# SH2_-_MCU.net
KiCad netlist of a schematic drawn in Altium Designer
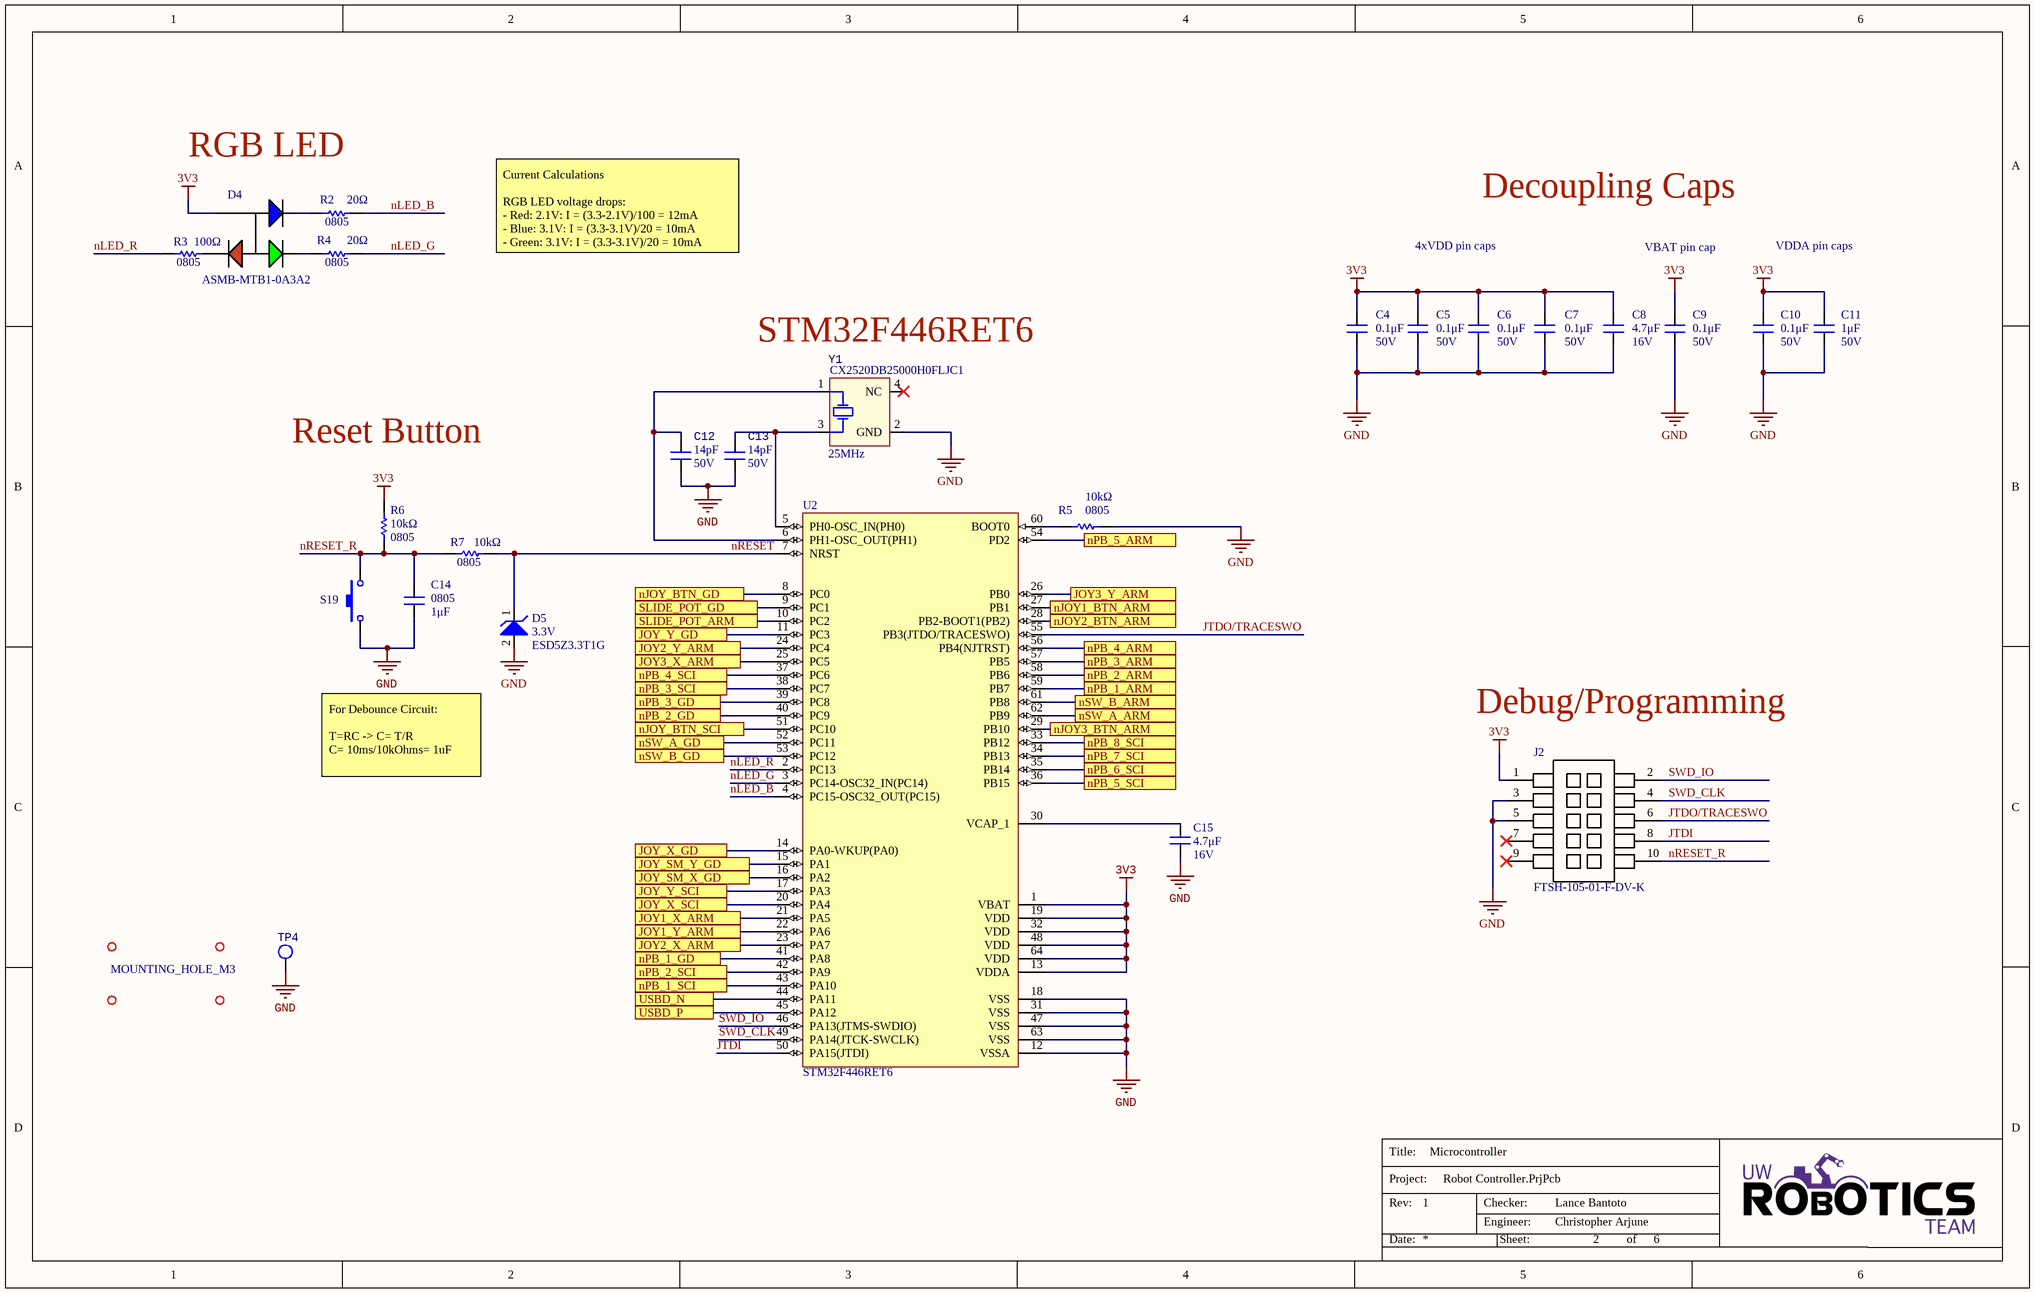
[diagram p0: SH2 - MCU.SchDoc]

(export (version "E")
  (design (tool "Eeschema 10.0.6"))
  (components
    (comp (ref "C4")
      (value "0.1μF")
      (footprint "CAP2012")
      (description "CAP CER 0.1UF 50V X7R 0805")
      (fields
        (field (name "VOLTAGE RATING") "50V")
        (field (name "LCSC PART #") "C49678")
        (field (name "Comment") "CAP_0.1uF_50V_0805")
      )
      (libsource (lib "UWRT_Schematic_Library_2020") (part "CAP_0.1uF_50V_0805"))
    )
    (comp (ref "C5")
      (value "0.1μF")
      (footprint "CAP2012")
      (description "CAP CER 0.1UF 50V X7R 0805")
      (fields
        (field (name "VOLTAGE RATING") "50V")
        (field (name "LCSC PART #") "C49678")
        (field (name "Comment") "CAP_0.1uF_50V_0805")
      )
      (libsource (lib "UWRT_Schematic_Library_2020") (part "CAP_0.1uF_50V_0805"))
    )
    (comp (ref "C6")
      (value "0.1μF")
      (footprint "CAP2012")
      (description "CAP CER 0.1UF 50V X7R 0805")
      (fields
        (field (name "VOLTAGE RATING") "50V")
        (field (name "LCSC PART #") "C49678")
        (field (name "Comment") "CAP_0.1uF_50V_0805")
      )
      (libsource (lib "UWRT_Schematic_Library_2020") (part "CAP_0.1uF_50V_0805"))
    )
    (comp (ref "C7")
      (value "0.1μF")
      (footprint "CAP2012")
      (description "CAP CER 0.1UF 50V X7R 0805")
      (fields
        (field (name "VOLTAGE RATING") "50V")
        (field (name "LCSC PART #") "C49678")
        (field (name "Comment") "CAP_0.1uF_50V_0805")
      )
      (libsource (lib "UWRT_Schematic_Library_2020") (part "CAP_0.1uF_50V_0805"))
    )
    (comp (ref "C8")
      (value "4.7μF")
      (footprint "CAP2012")
      (description "CAP CER 4.7UF 16V X5R 0805")
      (fields
        (field (name "VOLTAGE RATING") "16V")
        (field (name "LCSC PART #") "C1779")
        (field (name "Comment") "CAP_4.7uF_16V_0805")
      )
      (libsource (lib "UWRT_Schematic_Library_2020") (part "CAP_4.7uF_16V_0805"))
    )
    (comp (ref "C9")
      (value "0.1μF")
      (footprint "CAP2012")
      (description "CAP CER 0.1UF 50V X7R 0805")
      (fields
        (field (name "VOLTAGE RATING") "50V")
        (field (name "LCSC PART #") "C49678")
        (field (name "Comment") "CAP_0.1uF_50V_0805")
      )
      (libsource (lib "UWRT_Schematic_Library_2020") (part "CAP_0.1uF_50V_0805"))
    )
    (comp (ref "C10")
      (value "0.1μF")
      (footprint "CAP2012")
      (description "CAP CER 0.1UF 50V X7R 0805")
      (fields
        (field (name "VOLTAGE RATING") "50V")
        (field (name "LCSC PART #") "C49678")
        (field (name "Comment") "CAP_0.1uF_50V_0805")
      )
      (libsource (lib "UWRT_Schematic_Library_2020") (part "CAP_0.1uF_50V_0805"))
    )
    (comp (ref "C11")
      (value "1μF")
      (footprint "CAP2012")
      (description "CAP CER 1UF 50V X7R 0805")
      (fields
        (field (name "VOLTAGE RATING") "50V")
        (field (name "LCSC PART #") "C28323")
        (field (name "Comment") "CAP_1uF_50V_0805")
      )
      (libsource (lib "UWRT_Schematic_Library_2020") (part "CAP_1uF_50V_0805"))
    )
    (comp (ref "C12")
      (value "14pF")
      (footprint "CAP0603")
      (description "CAP CER 14PF 50V C0G/NP0 0603")
      (fields (field (name "VOLTAGE RATING") "50V") (field (name "Comment") "CAP_14pF_50V_0603"))
      (libsource (lib "UWRT_Schematic_Library_2020") (part "CAP_14pF_50V_0603"))
    )
    (comp (ref "C13")
      (value "14pF")
      (footprint "CAP0603")
      (description "CAP CER 14PF 50V C0G/NP0 0603")
      (fields (field (name "VOLTAGE RATING") "50V") (field (name "Comment") "CAP_14pF_50V_0603"))
      (libsource (lib "UWRT_Schematic_Library_2020") (part "CAP_14pF_50V_0603"))
    )
    (comp (ref "C14")
      (value "1μF")
      (footprint "CAP2012")
      (description "CAP CER 1UF 50V X7R 0805")
      (fields
        (field (name "LCSC PART #") "C28323")
        (field (name "PACKAGE/FOOTPRINT") "0805")
        (field (name "Comment") "CAP_1uF_50V_0805")
      )
      (libsource (lib "UWRT_Schematic_Library_2020") (part "CAP_1uF_50V_0805"))
    )
    (comp (ref "C15")
      (value "4.7μF")
      (footprint "CAP2012")
      (description "CAP CER 4.7UF 16V X5R 0805")
      (fields
        (field (name "VOLTAGE RATING") "16V")
        (field (name "LCSC PART #") "C1779")
        (field (name "Comment") "CAP_4.7uF_16V_0805")
      )
      (libsource (lib "UWRT_Schematic_Library_2020") (part "CAP_4.7uF_16V_0805"))
    )
    (comp (ref "D4")
      (value "LED_RGB")
      (footprint "LED_RGB")
      (description "LED RGB DIFFUSED 4PLCC SMD")
      (fields (field (name "MANUFACTURER PART NUMBER 1") "ASMB-MTB1-0A3A2"))
      (libsource (lib "UWRT_Schematic_Library_2020") (part "LED_RGB"))
    )
    (comp (ref "D5")
      (value "TVS_DIODE_UNIDIR_3.3V")
      (description "TVS DIODE 3.3V 14.1V SOD523")
      (fields
        (field (name "MANUFACTURER PART NUMBER 1") "ESD5Z3.3T1G")
        (field (name "LCSC PART #") "C61148")
        (field (name "VOLTAGE - REVERSE STANDOFF (TYP)") "3.3V")
      )
      (libsource (lib "UWRT_Schematic_Library_2020") (part "TVS_DIODE_UNIDIR_3.3V"))
    )
    (comp (ref "J2")
      (value "CON_PROGRAMMING")
      (footprint "FTSH-105-01-F-DV-K-P-TR")
      (description "CONN HEADER SMD 10POS 1.27MM")
      (fields (field (name "MANUFACTURER PART NUMBER 1") "FTSH-105-01-F-DV-K"))
      (libsource (lib "UWRT_Schematic_Library_2020") (part "CON_PROGRAMMING"))
    )
    (comp (ref "MH1")
      (value "MOUNTING_HOLE_M3")
      (footprint "MOUNTING_HOLE_3mm")
      (libsource (lib "UWRT_Schematic_Library_2020") (part "MOUNTING_HOLE_M3"))
    )
    (comp (ref "MH2")
      (value "MOUNTING_HOLE_M3")
      (footprint "MOUNTING_HOLE_3mm")
      (libsource (lib "UWRT_Schematic_Library_2020") (part "MOUNTING_HOLE_M3"))
    )
    (comp (ref "MH3")
      (value "MOUNTING_HOLE_M3")
      (footprint "MOUNTING_HOLE_3mm")
      (libsource (lib "UWRT_Schematic_Library_2020") (part "MOUNTING_HOLE_M3"))
    )
    (comp (ref "MH4")
      (value "MOUNTING_HOLE_M3")
      (footprint "MOUNTING_HOLE_3mm")
      (libsource (lib "UWRT_Schematic_Library_2020") (part "MOUNTING_HOLE_M3"))
    )
    (comp (ref "R2")
      (value "20Ω")
      (footprint "RESC0805")
      (description "RES 20 OHM 1% 1/8W 0805")
      (fields
        (field (name "LCSC PART #") "C17581")
        (field (name "PACKAGE/FOOTPRINT") "0805")
        (field (name "Comment") "RES_20Ω_0805_1%")
      )
      (libsource (lib "UWRT_Schematic_Library_2020") (part "RES_20Ω_0805_1%"))
    )
    (comp (ref "R3")
      (value "100Ω")
      (footprint "RESC0805")
      (description "RES 100 OHM 1% 1/8W 0805")
      (fields
        (field (name "LCSC PART #") "C1790")
        (field (name "PACKAGE/FOOTPRINT") "0805")
        (field (name "Comment") "RES_100Ω_0805_1%")
      )
      (libsource (lib "UWRT_Schematic_Library_2020") (part "RES_100Ω_0805_1%"))
    )
    (comp (ref "R4")
      (value "20Ω")
      (footprint "RESC0805")
      (description "RES 20 OHM 1% 1/8W 0805")
      (fields
        (field (name "LCSC PART #") "C17581")
        (field (name "PACKAGE/FOOTPRINT") "0805")
        (field (name "Comment") "RES_20Ω_0805_1%")
      )
      (libsource (lib "UWRT_Schematic_Library_2020") (part "RES_20Ω_0805_1%"))
    )
    (comp (ref "R5")
      (value "10kΩ")
      (footprint "RESC0805")
      (description "RES 10K OHM 5% 1/8W 0805")
      (fields
        (field (name "LCSC PART #") "C17414")
        (field (name "PACKAGE/FOOTPRINT") "0805")
        (field (name "Comment") "RES_10kΩ_0805_5%")
      )
      (libsource (lib "UWRT_Schematic_Library_2020") (part "RES_10kΩ_0805_5%"))
    )
    (comp (ref "R6")
      (value "10kΩ")
      (footprint "RESC0805")
      (description "RES 10K OHM 5% 1/8W 0805")
      (fields
        (field (name "LCSC PART #") "C17414")
        (field (name "PACKAGE/FOOTPRINT") "0805")
        (field (name "Comment") "RES_10kΩ_0805_5%")
      )
      (libsource (lib "UWRT_Schematic_Library_2020") (part "RES_10kΩ_0805_5%"))
    )
    (comp (ref "R7")
      (value "10kΩ")
      (footprint "RESC0805")
      (description "RES 10K OHM 5% 1/8W 0805")
      (fields
        (field (name "LCSC PART #") "C17414")
        (field (name "PACKAGE/FOOTPRINT") "0805")
        (field (name "Comment") "RES_10kΩ_0805_5%")
      )
      (libsource (lib "UWRT_Schematic_Library_2020") (part "RES_10kΩ_0805_5%"))
    )
    (comp (ref "S19")
      (value "SW_TACTILE")
      (footprint "B3U-1000P")
      (description "SWITCH TACTILE SPST-NO 0.05A 12V")
      (libsource (lib "UWRT_Schematic_Library_2020") (part "SW_TACTILE"))
    )
    (comp (ref "TP4")
      (value "TESTPOINT_LOOP")
      (footprint "TESTPOINT_LOOP")
      (description "TESTPOINT THRUHOLE")
      (libsource (lib "UWRT_Schematic_Library_2020") (part "TESTPOINT_LOOP"))
    )
    (comp (ref "U2")
      (value "STM32F446RET6")
      (footprint "STM-LQFP64_L")
      (libsource (lib "UWRT_Schematic_Library_2020") (part "MCU_STM32F446RET6"))
    )
    (comp (ref "Y1")
      (value "CRYSTAL_25MHZ")
      (footprint "SOIC254P1016X440-4N")
      (description "CRYSTAL 25.0000MHZ 12PF SMD")
      (fields
        (field (name "MANUFACTURER PART NUMBER 1") "CX2520DB25000H0FLJC1")
        (field (name "FREQUENCY") "25MHz")
      )
      (libsource (lib "UWRT_Schematic_Library_2020") (part "CRYSTAL_25MHZ"))
    )
  )
  (nets
    (net (code "1") (name "/JOY1_X_ARM") (class "Default")
      (node (ref "U2") (pin "21") (pinfunction "PA5_21") (pintype "bidirectional"))
    )
    (net (code "2") (name "/JOY1_Y_ARM") (class "Default")
      (node (ref "U2") (pin "22") (pinfunction "PA6_22") (pintype "bidirectional"))
    )
    (net (code "3") (name "/JOY2_X_ARM") (class "Default")
      (node (ref "U2") (pin "23") (pinfunction "PA7_23") (pintype "bidirectional"))
    )
    (net (code "4") (name "/JOY2_Y_ARM") (class "Default")
      (node (ref "U2") (pin "24") (pinfunction "PC4_24") (pintype "bidirectional"))
    )
    (net (code "5") (name "/JOY3_X_ARM") (class "Default")
      (node (ref "U2") (pin "25") (pinfunction "PC5_25") (pintype "bidirectional"))
    )
    (net (code "6") (name "/JOY3_Y_ARM") (class "Default")
      (node (ref "U2") (pin "26") (pinfunction "PB0_26") (pintype "bidirectional"))
    )
    (net (code "7") (name "/JOY_SM_X_GD") (class "Default")
      (node (ref "U2") (pin "16") (pinfunction "PA2_16") (pintype "bidirectional"))
    )
    (net (code "8") (name "/JOY_SM_Y_GD") (class "Default")
      (node (ref "U2") (pin "15") (pinfunction "PA1_15") (pintype "bidirectional"))
    )
    (net (code "9") (name "/JOY_X_GD") (class "Default")
      (node (ref "U2") (pin "14") (pinfunction "PA0-WKUP(PA0)_14") (pintype "bidirectional"))
    )
    (net (code "10") (name "/JOY_X_SCI") (class "Default")
      (node (ref "U2") (pin "20") (pinfunction "PA4_20") (pintype "bidirectional"))
    )
    (net (code "11") (name "/JOY_Y_GD") (class "Default")
      (node (ref "U2") (pin "11") (pinfunction "PC3_11") (pintype "bidirectional"))
    )
    (net (code "12") (name "/JOY_Y_SCI") (class "Default")
      (node (ref "U2") (pin "17") (pinfunction "PA3_17") (pintype "bidirectional"))
    )
    (net (code "13") (name "/JTDI") (class "Default")
      (node (ref "J2") (pin "8") (pinfunction "8_8") (pintype "passive"))
      (node (ref "U2") (pin "50") (pinfunction "PA15(JTDI)_50") (pintype "bidirectional"))
    )
    (net (code "14") (name "/JTDO{slash}TRACESWO") (class "Default")
      (node (ref "J2") (pin "6") (pinfunction "6_6") (pintype "passive"))
      (node (ref "U2") (pin "55") (pinfunction "PB3(JTDO/TRACESWO)_55") (pintype "bidirectional"))
    )
    (net (code "15") (name "/SLIDE_POT_ARM") (class "Default")
      (node (ref "U2") (pin "10") (pinfunction "PC2_10") (pintype "bidirectional"))
    )
    (net (code "16") (name "/SLIDE_POT_GD") (class "Default")
      (node (ref "U2") (pin "9") (pinfunction "PC1_9") (pintype "bidirectional"))
    )
    (net (code "17") (name "/SWD_CLK") (class "Default")
      (node (ref "J2") (pin "4") (pinfunction "4_4") (pintype "passive"))
      (node (ref "U2") (pin "49") (pinfunction "PA14(JTCK-SWCLK)_49") (pintype "bidirectional"))
    )
    (net (code "18") (name "/SWD_IO") (class "Default")
      (node (ref "J2") (pin "2") (pinfunction "2_2") (pintype "passive"))
      (node (ref "U2") (pin "46") (pinfunction "PA13(JTMS-SWDIO)_46") (pintype "bidirectional"))
    )
    (net (code "19") (name "/USBD_N") (class "Default")
      (node (ref "U2") (pin "44") (pinfunction "PA11_44") (pintype "bidirectional"))
    )
    (net (code "20") (name "/USBD_P") (class "Default")
      (node (ref "U2") (pin "45") (pinfunction "PA12_45") (pintype "bidirectional"))
    )
    (net (code "21") (name "/nJOY1_BTN_ARM") (class "Default")
      (node (ref "U2") (pin "27") (pinfunction "PB1_27") (pintype "bidirectional"))
    )
    (net (code "22") (name "/nJOY2_BTN_ARM") (class "Default")
      (node (ref "U2") (pin "28") (pinfunction "PB2-BOOT1(PB2)_28") (pintype "bidirectional"))
    )
    (net (code "23") (name "/nJOY3_BTN_ARM") (class "Default")
      (node (ref "U2") (pin "29") (pinfunction "PB10_29") (pintype "bidirectional"))
    )
    (net (code "24") (name "/nJOY_BTN_GD") (class "Default")
      (node (ref "U2") (pin "8") (pinfunction "PC0_8") (pintype "bidirectional"))
    )
    (net (code "25") (name "/nJOY_BTN_SCI") (class "Default")
      (node (ref "U2") (pin "51") (pinfunction "PC10_51") (pintype "bidirectional"))
    )
    (net (code "26") (name "/nLED_B") (class "Default")
      (node (ref "R2") (pin "2") (pinfunction "2_2") (pintype "passive"))
      (node (ref "U2") (pin "4") (pinfunction "PC15-OSC32_OUT(PC15)_4") (pintype "bidirectional"))
    )
    (net (code "27") (name "/nLED_G") (class "Default")
      (node (ref "R4") (pin "2") (pinfunction "2_2") (pintype "passive"))
      (node (ref "U2") (pin "3") (pinfunction "PC14-OSC32_IN(PC14)_3") (pintype "bidirectional"))
    )
    (net (code "28") (name "/nLED_R") (class "Default")
      (node (ref "R3") (pin "1") (pinfunction "1_1") (pintype "passive"))
      (node (ref "U2") (pin "2") (pinfunction "PC13_2") (pintype "bidirectional"))
    )
    (net (code "29") (name "/nPB_1_ARM") (class "Default")
      (node (ref "U2") (pin "59") (pinfunction "PB7_59") (pintype "bidirectional"))
    )
    (net (code "30") (name "/nPB_1_GD") (class "Default")
      (node (ref "U2") (pin "41") (pinfunction "PA8_41") (pintype "bidirectional"))
    )
    (net (code "31") (name "/nPB_1_SCI") (class "Default")
      (node (ref "U2") (pin "43") (pinfunction "PA10_43") (pintype "bidirectional"))
    )
    (net (code "32") (name "/nPB_2_ARM") (class "Default")
      (node (ref "U2") (pin "58") (pinfunction "PB6_58") (pintype "bidirectional"))
    )
    (net (code "33") (name "/nPB_2_GD") (class "Default")
      (node (ref "U2") (pin "40") (pinfunction "PC9_40") (pintype "bidirectional"))
    )
    (net (code "34") (name "/nPB_2_SCI") (class "Default")
      (node (ref "U2") (pin "42") (pinfunction "PA9_42") (pintype "bidirectional"))
    )
    (net (code "35") (name "/nPB_3_ARM") (class "Default")
      (node (ref "U2") (pin "57") (pinfunction "PB5_57") (pintype "bidirectional"))
    )
    (net (code "36") (name "/nPB_3_GD") (class "Default")
      (node (ref "U2") (pin "39") (pinfunction "PC8_39") (pintype "bidirectional"))
    )
    (net (code "37") (name "/nPB_3_SCI") (class "Default")
      (node (ref "U2") (pin "38") (pinfunction "PC7_38") (pintype "bidirectional"))
    )
    (net (code "38") (name "/nPB_4_ARM") (class "Default")
      (node (ref "U2") (pin "56") (pinfunction "PB4(NJTRST)_56") (pintype "bidirectional"))
    )
    (net (code "39") (name "/nPB_4_SCI") (class "Default")
      (node (ref "U2") (pin "37") (pinfunction "PC6_37") (pintype "bidirectional"))
    )
    (net (code "40") (name "/nPB_5_ARM") (class "Default")
      (node (ref "U2") (pin "54") (pinfunction "PD2_54") (pintype "bidirectional"))
    )
    (net (code "41") (name "/nPB_5_SCI") (class "Default")
      (node (ref "U2") (pin "36") (pinfunction "PB15_36") (pintype "bidirectional"))
    )
    (net (code "42") (name "/nPB_6_SCI") (class "Default")
      (node (ref "U2") (pin "35") (pinfunction "PB14_35") (pintype "bidirectional"))
    )
    (net (code "43") (name "/nPB_7_SCI") (class "Default")
      (node (ref "U2") (pin "34") (pinfunction "PB13_34") (pintype "bidirectional"))
    )
    (net (code "44") (name "/nPB_8_SCI") (class "Default")
      (node (ref "U2") (pin "33") (pinfunction "PB12_33") (pintype "bidirectional"))
    )
    (net (code "45") (name "/nRESET") (class "Default")
      (node (ref "D5") (pin "1") (pinfunction "1_1") (pintype "passive"))
      (node (ref "R7") (pin "2") (pinfunction "2_2") (pintype "passive"))
      (node (ref "U2") (pin "7") (pinfunction "NRST_7") (pintype "bidirectional"))
    )
    (net (code "46") (name "/nRESET_R") (class "Default")
      (node (ref "C14") (pin "2") (pinfunction "2_2") (pintype "passive"))
      (node (ref "J2") (pin "10") (pinfunction "10_10") (pintype "passive"))
      (node (ref "R6") (pin "1") (pinfunction "1_1") (pintype "passive"))
      (node (ref "R7") (pin "1") (pinfunction "1_1") (pintype "passive"))
      (node (ref "S19") (pin "1") (pinfunction "1_1") (pintype "passive"))
    )
    (net (code "47") (name "/nSW_A_ARM") (class "Default")
      (node (ref "U2") (pin "62") (pinfunction "PB9_62") (pintype "bidirectional"))
    )
    (net (code "48") (name "/nSW_A_GD") (class "Default")
      (node (ref "U2") (pin "52") (pinfunction "PC11_52") (pintype "bidirectional"))
    )
    (net (code "49") (name "/nSW_B_ARM") (class "Default")
      (node (ref "U2") (pin "61") (pinfunction "PB8_61") (pintype "bidirectional"))
    )
    (net (code "50") (name "/nSW_B_GD") (class "Default")
      (node (ref "U2") (pin "53") (pinfunction "PC12_53") (pintype "bidirectional"))
    )
    (net (code "51") (name "3V3") (class "Default")
      (node (ref "C10") (pin "2") (pinfunction "2_2") (pintype "passive"))
      (node (ref "C11") (pin "2") (pinfunction "2_2") (pintype "passive"))
      (node (ref "C4") (pin "2") (pinfunction "2_2") (pintype "passive"))
      (node (ref "C5") (pin "2") (pinfunction "2_2") (pintype "passive"))
      (node (ref "C6") (pin "2") (pinfunction "2_2") (pintype "passive"))
      (node (ref "C7") (pin "2") (pinfunction "2_2") (pintype "passive"))
      (node (ref "C8") (pin "2") (pinfunction "2_2") (pintype "passive"))
      (node (ref "C9") (pin "2") (pinfunction "2_2") (pintype "passive"))
      (node (ref "D4") (pin "4") (pinfunction "COMMON_ANODE_4") (pintype "passive"))
      (node (ref "J2") (pin "1") (pinfunction "1_1") (pintype "passive"))
      (node (ref "R6") (pin "2") (pinfunction "2_2") (pintype "passive"))
      (node (ref "U2") (pin "1") (pinfunction "VBAT_1") (pintype "power_in"))
      (node (ref "U2") (pin "13") (pinfunction "VDDA_13") (pintype "power_in"))
      (node (ref "U2") (pin "19") (pinfunction "VDD_19") (pintype "power_in"))
      (node (ref "U2") (pin "32") (pinfunction "VDD_32") (pintype "power_in"))
      (node (ref "U2") (pin "48") (pinfunction "VDD_48") (pintype "power_in"))
      (node (ref "U2") (pin "64") (pinfunction "VDD_64") (pintype "power_in"))
    )
    (net (code "52") (name "GND") (class "Default")
      (node (ref "C10") (pin "1") (pinfunction "1_1") (pintype "passive"))
      (node (ref "C11") (pin "1") (pinfunction "1_1") (pintype "passive"))
      (node (ref "C12") (pin "1") (pinfunction "1_1") (pintype "passive"))
      (node (ref "C13") (pin "1") (pinfunction "1_1") (pintype "passive"))
      (node (ref "C14") (pin "1") (pinfunction "1_1") (pintype "passive"))
      (node (ref "C15") (pin "1") (pinfunction "1_1") (pintype "passive"))
      (node (ref "C4") (pin "1") (pinfunction "1_1") (pintype "passive"))
      (node (ref "C5") (pin "1") (pinfunction "1_1") (pintype "passive"))
      (node (ref "C6") (pin "1") (pinfunction "1_1") (pintype "passive"))
      (node (ref "C7") (pin "1") (pinfunction "1_1") (pintype "passive"))
      (node (ref "C8") (pin "1") (pinfunction "1_1") (pintype "passive"))
      (node (ref "C9") (pin "1") (pinfunction "1_1") (pintype "passive"))
      (node (ref "D5") (pin "2") (pinfunction "2_2") (pintype "passive"))
      (node (ref "J2") (pin "3") (pinfunction "3_3") (pintype "passive"))
      (node (ref "J2") (pin "5") (pinfunction "5_5") (pintype "passive"))
      (node (ref "R5") (pin "2") (pinfunction "2_2") (pintype "passive"))
      (node (ref "S19") (pin "2") (pinfunction "2_2") (pintype "passive"))
      (node (ref "TP4") (pin "1") (pintype "passive"))
      (node (ref "U2") (pin "12") (pinfunction "VSSA_12") (pintype "power_in"))
      (node (ref "U2") (pin "18") (pinfunction "VSS_18") (pintype "power_in"))
      (node (ref "U2") (pin "31") (pinfunction "VSS_31") (pintype "power_in"))
      (node (ref "U2") (pin "47") (pinfunction "VSS_47") (pintype "power_in"))
      (node (ref "U2") (pin "63") (pinfunction "VSS_63") (pintype "power_in"))
      (node (ref "Y1") (pin "2") (pinfunction "GND_2") (pintype "power_in"))
    )
    (net (code "53") (name "Net-(D4-CATHODE_(BLUE))") (class "Default")
      (node (ref "D4") (pin "3") (pinfunction "CATHODE_(BLUE)_3") (pintype "passive"))
      (node (ref "R2") (pin "1") (pinfunction "1_1") (pintype "passive"))
    )
    (net (code "54") (name "Net-(D4-CATHODE_(GREEN))") (class "Default")
      (node (ref "D4") (pin "2") (pinfunction "CATHODE_(GREEN)_2") (pintype "passive"))
      (node (ref "R4") (pin "1") (pinfunction "1_1") (pintype "passive"))
    )
    (net (code "55") (name "Net-(D4-CATHODE_(RED))") (class "Default")
      (node (ref "D4") (pin "1") (pinfunction "CATHODE_(RED)_1") (pintype "passive"))
      (node (ref "R3") (pin "2") (pinfunction "2_2") (pintype "passive"))
    )
    (net (code "56") (name "Net-(U2-BOOT0)") (class "Default")
      (node (ref "R5") (pin "1") (pinfunction "1_1") (pintype "passive"))
      (node (ref "U2") (pin "60") (pinfunction "BOOT0_60") (pintype "input"))
    )
    (net (code "57") (name "Net-(U2-PH0-OSC_IN(PH0))") (class "Default")
      (node (ref "C13") (pin "2") (pinfunction "2_2") (pintype "passive"))
      (node (ref "U2") (pin "5") (pinfunction "PH0-OSC_IN(PH0)_5") (pintype "bidirectional"))
      (node (ref "Y1") (pin "3") (pinfunction "HOT_3") (pintype "passive"))
    )
    (net (code "58") (name "Net-(U2-PH1-OSC_OUT(PH1))") (class "Default")
      (node (ref "C12") (pin "2") (pinfunction "2_2") (pintype "passive"))
      (node (ref "U2") (pin "6") (pinfunction "PH1-OSC_OUT(PH1)_6") (pintype "bidirectional"))
      (node (ref "Y1") (pin "1") (pinfunction "HOT_1") (pintype "passive"))
    )
    (net (code "59") (name "Net-(U2-VCAP_1)") (class "Default")
      (node (ref "C15") (pin "2") (pinfunction "2_2") (pintype "passive"))
      (node (ref "U2") (pin "30") (pinfunction "VCAP_1_30") (pintype "passive"))
    )
    (net (code "60") (name "unconnected-(J2-Pad7)") (class "Default")
      (node (ref "J2") (pin "7") (pinfunction "7_7") (pintype "passive+no_connect"))
    )
    (net (code "61") (name "unconnected-(J2-Pad9)") (class "Default")
      (node (ref "J2") (pin "9") (pinfunction "9_9") (pintype "passive+no_connect"))
    )
    (net (code "62") (name "unconnected-(Y1-NC-Pad4)") (class "Default")
      (node (ref "Y1") (pin "4") (pinfunction "NC_4") (pintype "passive+no_connect"))
    )
  )
)
